# Power_IR2153.net
KiCad netlist of a schematic drawn in EAGLE
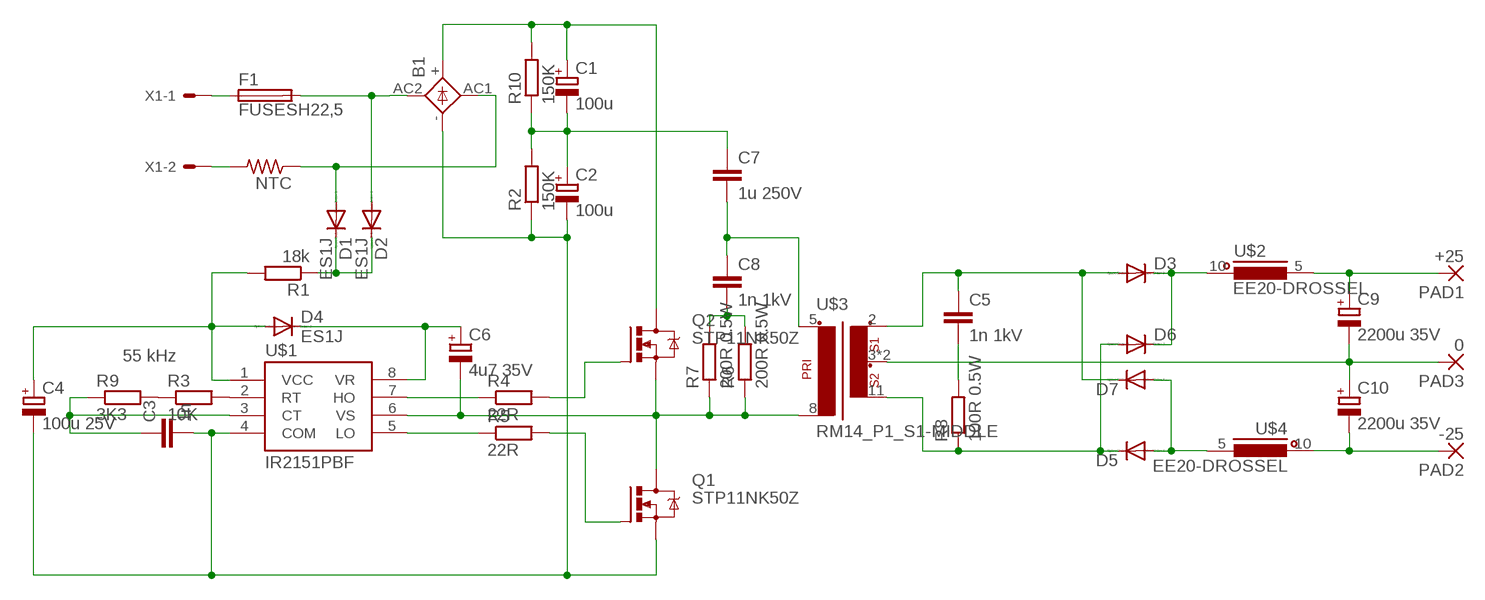
[diagram p0: schematic, sheet 1]

(export (version "E")
  (design (tool "Eeschema 10.0.6"))
  (components
    (comp (ref "B1")
      (value "KBL")
      (footprint "eagle-import:KBL")
      (libsource (lib "eagle-import") (part "KBL"))
    )
    (comp (ref "C1")
      (value "100u")
      (footprint "eagle-import:EB22,5D")
      (libsource (lib "eagle-import") (part "CPOL-EUE10-22.5"))
    )
    (comp (ref "C2")
      (value "100u")
      (footprint "eagle-import:EB22,5D")
      (libsource (lib "eagle-import") (part "CPOL-EUE10-22.5"))
    )
    (comp (ref "C3")
      (value "1n")
      (footprint "eagle-import:C1206")
      (libsource (lib "eagle-import") (part "C-EUC1206"))
    )
    (comp (ref "C4")
      (value "100u 25V")
      (footprint "eagle-import:E2,5-7")
      (libsource (lib "eagle-import") (part "CPOL-EUE2.5-7"))
    )
    (comp (ref "C5")
      (value "1n 1kV")
      (footprint "eagle-import:C050-025X075")
      (libsource (lib "eagle-import") (part "C-EU050-025X075"))
    )
    (comp (ref "C6")
      (value "4u7 35V")
      (footprint "eagle-import:E2,5-5")
      (libsource (lib "eagle-import") (part "CPOL-EUE2.5-5"))
    )
    (comp (ref "C7")
      (value "1u 250V")
      (footprint "eagle-import:C225-074X268")
      (libsource (lib "eagle-import") (part "C-EU225-074X268"))
    )
    (comp (ref "C8")
      (value "1n 1kV")
      (footprint "eagle-import:C050-025X075")
      (libsource (lib "eagle-import") (part "C-EU050-025X075"))
    )
    (comp (ref "C9")
      (value "2200u 35V")
      (footprint "eagle-import:E7,5-16")
      (libsource (lib "eagle-import") (part "CPOL-EUE7.5-16"))
    )
    (comp (ref "C10")
      (value "2200u 35V")
      (footprint "eagle-import:E7,5-16")
      (libsource (lib "eagle-import") (part "CPOL-EUE7.5-16"))
    )
    (comp (ref "D1")
      (value "ES1J")
      (footprint "eagle-import:DO-214AC")
      (libsource (lib "eagle-import") (part "DIODE-DO-214AC"))
    )
    (comp (ref "D2")
      (value "ES1J")
      (footprint "eagle-import:DO-214AC")
      (libsource (lib "eagle-import") (part "DIODE-DO-214AC"))
    )
    (comp (ref "D3")
      (value "DIODE-SMB")
      (footprint "eagle-import:SMB")
      (libsource (lib "eagle-import") (part "DIODE-SMB"))
    )
    (comp (ref "D4")
      (value "ES1J")
      (footprint "eagle-import:DO-214AC")
      (libsource (lib "eagle-import") (part "DIODE-DO-214AC"))
    )
    (comp (ref "D5")
      (value "DIODE-SMB")
      (footprint "eagle-import:SMB")
      (libsource (lib "eagle-import") (part "DIODE-SMB"))
    )
    (comp (ref "D6")
      (value "DIODE-SMB")
      (footprint "eagle-import:SMB")
      (libsource (lib "eagle-import") (part "DIODE-SMB"))
    )
    (comp (ref "D7")
      (value "DIODE-SMB")
      (footprint "eagle-import:SMB")
      (libsource (lib "eagle-import") (part "DIODE-SMB"))
    )
    (comp (ref "F1")
      (value "FUSESH22,5")
      (footprint "eagle-import:SH22,5")
      (fields (field (name "MF") "SCHURTER") (field (name "MPN") "0031.8201"))
      (libsource (lib "eagle-import") (part "SH22,5"))
    )
    (comp (ref "NTC")
      (value "R-US_0207/10")
      (footprint "eagle-import:0207_10")
      (libsource (lib "eagle-import") (part "R-US_0207/10"))
    )
    (comp (ref "PAD1")
      (value "+25")
      (footprint "eagle-import:2,54_0,8")
      (libsource (lib "eagle-import") (part "2,54/0,8"))
    )
    (comp (ref "PAD2")
      (value "-25")
      (footprint "eagle-import:2,54_0,8")
      (libsource (lib "eagle-import") (part "2,54/0,8"))
    )
    (comp (ref "PAD3")
      (value "0")
      (footprint "eagle-import:2,54_0,8")
      (libsource (lib "eagle-import") (part "2,54/0,8"))
    )
    (comp (ref "Q1")
      (value "STP11NK50Z")
      (footprint "eagle-import:TO220BV")
      (libsource (lib "eagle-import") (part "IRF740"))
    )
    (comp (ref "Q2")
      (value "STP11NK50Z")
      (footprint "eagle-import:TO220BV")
      (libsource (lib "eagle-import") (part "IRF740"))
    )
    (comp (ref "R1")
      (value "18k")
      (footprint "eagle-import:0922_22")
      (libsource (lib "eagle-import") (part "R-EU_0922/22"))
    )
    (comp (ref "R2")
      (value "150K")
      (footprint "eagle-import:0207_10")
      (libsource (lib "eagle-import") (part "R-EU_0207/10"))
    )
    (comp (ref "R3")
      (value "10K")
      (footprint "eagle-import:R1206")
      (libsource (lib "eagle-import") (part "R-EU_R1206"))
    )
    (comp (ref "R4")
      (value "22R")
      (footprint "eagle-import:R1206")
      (libsource (lib "eagle-import") (part "R-EU_R1206"))
    )
    (comp (ref "R5")
      (value "22R")
      (footprint "eagle-import:R1206")
      (libsource (lib "eagle-import") (part "R-EU_R1206"))
    )
    (comp (ref "R6")
      (value "200R 0.5W")
      (footprint "eagle-import:0207_10")
      (libsource (lib "eagle-import") (part "R-EU_0207/10"))
    )
    (comp (ref "R7")
      (value "200R 0.5W")
      (footprint "eagle-import:0207_10")
      (libsource (lib "eagle-import") (part "R-EU_0207/10"))
    )
    (comp (ref "R8")
      (value "100R 0.5W")
      (footprint "eagle-import:0207_10")
      (libsource (lib "eagle-import") (part "R-EU_0207/10"))
    )
    (comp (ref "R9")
      (value "3K3")
      (footprint "eagle-import:R1206")
      (libsource (lib "eagle-import") (part "R-EU_R1206"))
    )
    (comp (ref "R10")
      (value "150K")
      (footprint "eagle-import:0207_10")
      (libsource (lib "eagle-import") (part "R-EU_0207/10"))
    )
    (comp (ref "U$1")
      (value "IR2151PBF")
      (footprint "eagle-import:DIP-8")
      (libsource (lib "eagle-import") (part "IR2151PBF"))
    )
    (comp (ref "U$2")
      (value "EE20-DROSSEL")
      (footprint "eagle-import:EE20_DROSSEL")
      (libsource (lib "eagle-import") (part "EE20-DROSSEL"))
    )
    (comp (ref "U$3")
      (value "RM14_P1_S1-MIDDLE")
      (footprint "eagle-import:RM14")
      (libsource (lib "eagle-import") (part "RM14_P1_S1-MIDDLE"))
    )
    (comp (ref "U$4")
      (value "EE20-DROSSEL")
      (footprint "eagle-import:EE20_DROSSEL")
      (libsource (lib "eagle-import") (part "EE20-DROSSEL"))
    )
    (comp (ref "X1")
      (value "KK-156-2")
      (footprint "eagle-import:KK-156-2")
      (libsource (lib "eagle-import") (part "KK-156-2"))
    )
  )
  (nets
    (net (code "1") (name "Net-(B1-AC1)") (class "Default")
      (node (ref "B1") (pin "AC2") (pinfunction "AC1_AC2") (pintype "passive"))
      (node (ref "D2") (pin "A") (pinfunction "A_A") (pintype "passive"))
      (node (ref "F1") (pin "2") (pinfunction "2_2") (pintype "passive"))
    )
    (net (code "2") (name "Net-(B1-AC2)") (class "Default")
      (node (ref "B1") (pin "AC1") (pinfunction "AC2_AC1") (pintype "passive"))
      (node (ref "D1") (pin "A") (pinfunction "A_A") (pintype "passive"))
      (node (ref "NTC") (pin "1") (pinfunction "1_1") (pintype "passive"))
    )
    (net (code "3") (name "Net-(B1-Pad+)") (class "Default")
      (node (ref "B1") (pin "+") (pinfunction "+_+") (pintype "passive"))
      (node (ref "C1") (pin "+") (pinfunction "+_+") (pintype "passive"))
      (node (ref "Q2") (pin "D") (pinfunction "D_D") (pintype "passive"))
      (node (ref "R10") (pin "2") (pinfunction "2_2") (pintype "passive"))
    )
    (net (code "4") (name "Net-(C1-Pad-)") (class "Default")
      (node (ref "C1") (pin "-") (pinfunction "-_-") (pintype "passive"))
      (node (ref "C2") (pin "+") (pinfunction "+_+") (pintype "passive"))
      (node (ref "C7") (pin "1") (pinfunction "1_1") (pintype "passive"))
      (node (ref "R10") (pin "1") (pinfunction "1_1") (pintype "passive"))
      (node (ref "R2") (pin "2") (pinfunction "2_2") (pintype "passive"))
    )
    (net (code "5") (name "Net-(C5-Pad2)") (class "Default")
      (node (ref "C5") (pin "2") (pinfunction "2_2") (pintype "passive"))
      (node (ref "R8") (pin "2") (pinfunction "2_2") (pintype "passive"))
    )
    (net (code "6") (name "Net-(C8-Pad2)") (class "Default")
      (node (ref "C8") (pin "2") (pinfunction "2_2") (pintype "passive"))
      (node (ref "R6") (pin "2") (pinfunction "2_2") (pintype "passive"))
      (node (ref "R7") (pin "2") (pinfunction "2_2") (pintype "passive"))
    )
    (net (code "7") (name "Net-(D1-PadC)") (class "Default")
      (node (ref "D1") (pin "C") (pinfunction "C_C") (pintype "passive"))
      (node (ref "D2") (pin "C") (pinfunction "C_C") (pintype "passive"))
      (node (ref "R1") (pin "1") (pinfunction "1_1") (pintype "passive"))
    )
    (net (code "8") (name "Net-(PAD1-P)") (class "Default")
      (node (ref "C9") (pin "+") (pinfunction "+_+") (pintype "passive"))
      (node (ref "PAD1") (pin "1") (pinfunction "P_1") (pintype "passive"))
      (node (ref "U$2") (pin "5") (pinfunction "2_5") (pintype "passive"))
    )
    (net (code "9") (name "Net-(PAD2-P)") (class "Default")
      (node (ref "C10") (pin "-") (pinfunction "-_-") (pintype "passive"))
      (node (ref "PAD2") (pin "1") (pinfunction "P_1") (pintype "passive"))
      (node (ref "U$4") (pin "10") (pinfunction "1_10") (pintype "passive"))
    )
    (net (code "10") (name "Net-(PAD3-P)") (class "Default")
      (node (ref "C10") (pin "+") (pinfunction "+_+") (pintype "passive"))
      (node (ref "C9") (pin "-") (pinfunction "-_-") (pintype "passive"))
      (node (ref "PAD3") (pin "1") (pinfunction "P_1") (pintype "passive"))
      (node (ref "U$3") (pin "10") (pinfunction "SM_10") (pintype "passive"))
      (node (ref "U$3") (pin "3") (pinfunction "SM_3") (pintype "passive"))
    )
    (net (code "11") (name "Net-(Q1-PadG)") (class "Default")
      (node (ref "Q1") (pin "G") (pinfunction "G_G") (pintype "passive"))
      (node (ref "R5") (pin "2") (pinfunction "2_2") (pintype "passive"))
    )
    (net (code "12") (name "Net-(Q2-PadG)") (class "Default")
      (node (ref "Q2") (pin "G") (pinfunction "G_G") (pintype "passive"))
      (node (ref "R4") (pin "2") (pinfunction "2_2") (pintype "passive"))
    )
    (net (code "13") (name "Net-(R3-Pad1)") (class "Default")
      (node (ref "R3") (pin "1") (pinfunction "1_1") (pintype "passive"))
      (node (ref "R9") (pin "2") (pinfunction "2_2") (pintype "passive"))
    )
    (net (code "14") (name "Net-(U$1-COM)") (class "Default")
      (node (ref "B1") (pin "-") (pinfunction "-_-") (pintype "passive"))
      (node (ref "C2") (pin "-") (pinfunction "-_-") (pintype "passive"))
      (node (ref "C3") (pin "2") (pinfunction "2_2") (pintype "passive"))
      (node (ref "C4") (pin "-") (pinfunction "-_-") (pintype "passive"))
      (node (ref "Q1") (pin "S") (pinfunction "S_S") (pintype "passive"))
      (node (ref "R2") (pin "1") (pinfunction "1_1") (pintype "passive"))
      (node (ref "U$1") (pin "4") (pinfunction "COM_4") (pintype "power_in"))
    )
    (net (code "15") (name "Net-(U$1-CT)") (class "Default")
      (node (ref "C3") (pin "1") (pinfunction "1_1") (pintype "passive"))
      (node (ref "R9") (pin "1") (pinfunction "1_1") (pintype "passive"))
      (node (ref "U$1") (pin "3") (pinfunction "CT_3") (pintype "power_in"))
    )
    (net (code "16") (name "Net-(U$1-HO)") (class "Default")
      (node (ref "R4") (pin "1") (pinfunction "1_1") (pintype "passive"))
      (node (ref "U$1") (pin "7") (pinfunction "HO_7") (pintype "power_in"))
    )
    (net (code "17") (name "Net-(U$1-LO)") (class "Default")
      (node (ref "R5") (pin "1") (pinfunction "1_1") (pintype "passive"))
      (node (ref "U$1") (pin "5") (pinfunction "LO_5") (pintype "power_in"))
    )
    (net (code "18") (name "Net-(U$1-RT)") (class "Default")
      (node (ref "R3") (pin "2") (pinfunction "2_2") (pintype "passive"))
      (node (ref "U$1") (pin "2") (pinfunction "RT_2") (pintype "power_in"))
    )
    (net (code "19") (name "Net-(U$1-VCC)") (class "Default")
      (node (ref "C4") (pin "+") (pinfunction "+_+") (pintype "passive"))
      (node (ref "D4") (pin "A") (pinfunction "A_A") (pintype "passive"))
      (node (ref "R1") (pin "2") (pinfunction "2_2") (pintype "passive"))
      (node (ref "U$1") (pin "1") (pinfunction "VCC_1") (pintype "power_in"))
    )
    (net (code "20") (name "Net-(U$1-VR)") (class "Default")
      (node (ref "C6") (pin "+") (pinfunction "+_+") (pintype "passive"))
      (node (ref "D4") (pin "C") (pinfunction "C_C") (pintype "passive"))
      (node (ref "U$1") (pin "8") (pinfunction "VR_8") (pintype "power_in"))
    )
    (net (code "21") (name "Net-(U$1-VS)") (class "Default")
      (node (ref "C6") (pin "-") (pinfunction "-_-") (pintype "passive"))
      (node (ref "Q1") (pin "D") (pinfunction "D_D") (pintype "passive"))
      (node (ref "Q2") (pin "S") (pinfunction "S_S") (pintype "passive"))
      (node (ref "R6") (pin "1") (pinfunction "1_1") (pintype "passive"))
      (node (ref "R7") (pin "1") (pinfunction "1_1") (pintype "passive"))
      (node (ref "U$1") (pin "6") (pinfunction "VS_6") (pintype "power_in"))
      (node (ref "U$3") (pin "8") (pinfunction "P1-2_8") (pintype "passive"))
    )
    (net (code "22") (name "Net-(U$2-1)") (class "Default")
      (node (ref "D3") (pin "C") (pinfunction "C_C") (pintype "passive"))
      (node (ref "D6") (pin "C") (pinfunction "C_C") (pintype "passive"))
      (node (ref "U$2") (pin "10") (pinfunction "1_10") (pintype "passive"))
    )
    (net (code "23") (name "Net-(U$3-P1-1)") (class "Default")
      (node (ref "C7") (pin "2") (pinfunction "2_2") (pintype "passive"))
      (node (ref "C8") (pin "1") (pinfunction "1_1") (pintype "passive"))
      (node (ref "U$3") (pin "5") (pinfunction "P1-1_5") (pintype "passive"))
    )
    (net (code "24") (name "Net-(U$3-S1)") (class "Default")
      (node (ref "C5") (pin "1") (pinfunction "1_1") (pintype "passive"))
      (node (ref "D3") (pin "A") (pinfunction "A_A") (pintype "passive"))
      (node (ref "D7") (pin "C") (pinfunction "C_C") (pintype "passive"))
      (node (ref "U$3") (pin "2") (pinfunction "S1_2") (pintype "passive"))
    )
    (net (code "25") (name "Net-(U$3-S2)") (class "Default")
      (node (ref "D5") (pin "C") (pinfunction "C_C") (pintype "passive"))
      (node (ref "D6") (pin "A") (pinfunction "A_A") (pintype "passive"))
      (node (ref "R8") (pin "1") (pinfunction "1_1") (pintype "passive"))
      (node (ref "U$3") (pin "11") (pinfunction "S2_11") (pintype "passive"))
    )
    (net (code "26") (name "Net-(U$4-2)") (class "Default")
      (node (ref "D5") (pin "A") (pinfunction "A_A") (pintype "passive"))
      (node (ref "D7") (pin "A") (pinfunction "A_A") (pintype "passive"))
      (node (ref "U$4") (pin "5") (pinfunction "2_5") (pintype "passive"))
    )
    (net (code "27") (name "Net-(X1A-S)") (class "Default")
      (node (ref "F1") (pin "1") (pinfunction "1_1") (pintype "passive"))
      (node (ref "X1") (pin "1") (pinfunction "S_1") (pintype "passive"))
    )
    (net (code "28") (name "Net-(X1B-S)") (class "Default")
      (node (ref "NTC") (pin "2") (pinfunction "2_2") (pintype "passive"))
      (node (ref "X1") (pin "2") (pinfunction "S_2") (pintype "passive"))
    )
  )
)
